# PWM_sheild_d1_mini_v1.net
KiCad netlist of a schematic drawn in EAGLE
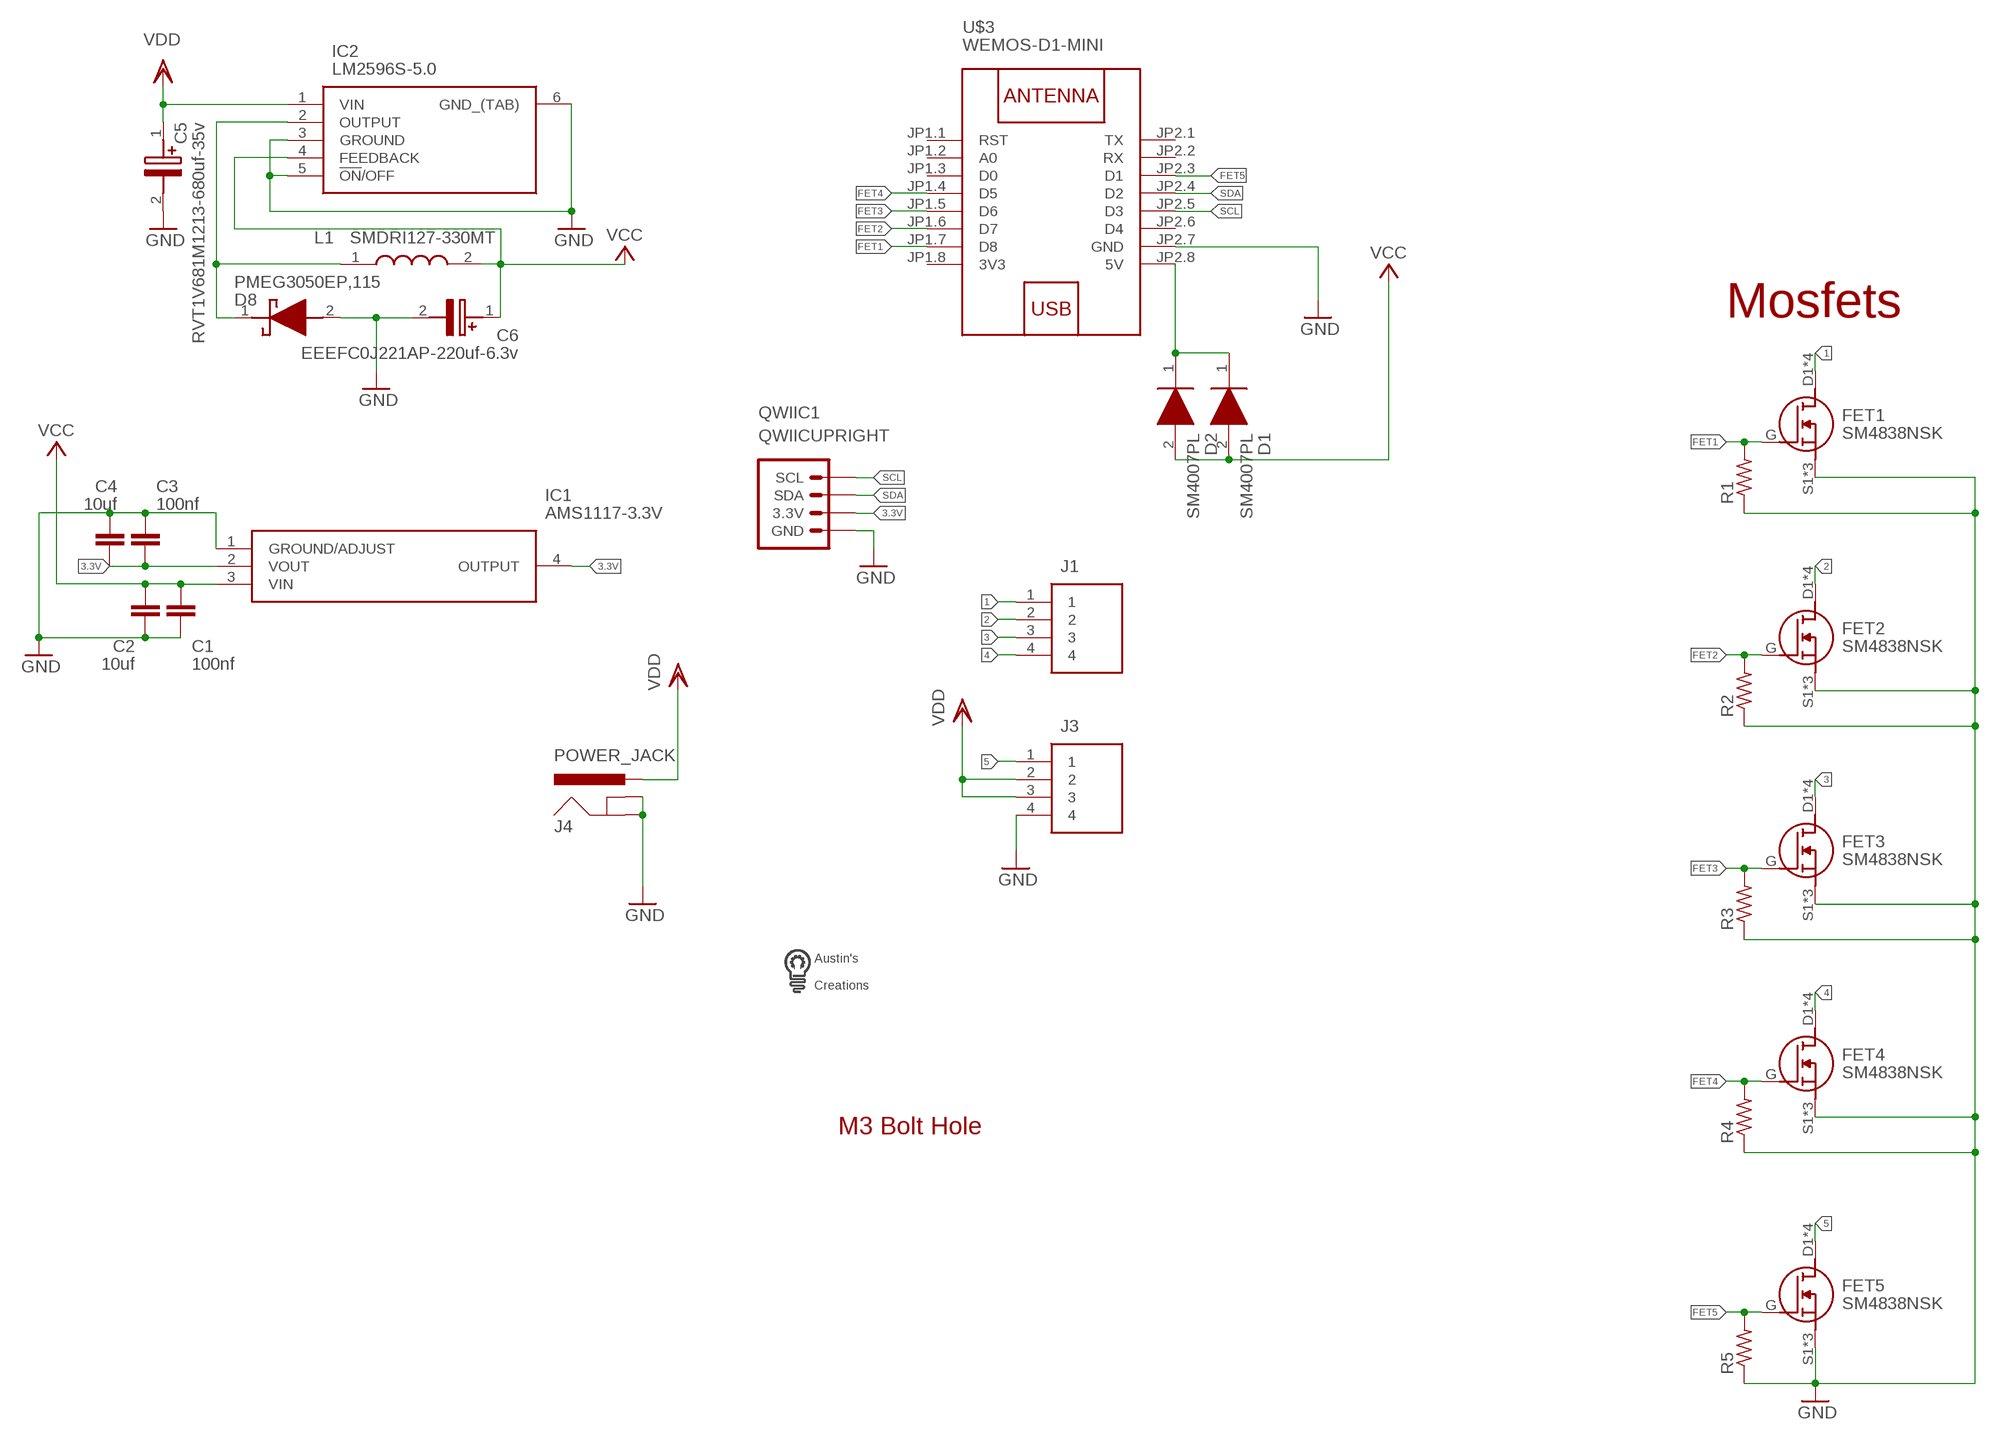
[diagram p0: schematic, sheet 1]

(export (version "E")
  (design (tool "Eeschema 10.0.6"))
  (components
    (comp (ref "C1")
      (value "100nf")
      (footprint "eagle-import:C0603")
      (libsource (lib "eagle-import") (part "C-EUC0603"))
    )
    (comp (ref "C2")
      (value "10uf")
      (footprint "eagle-import:C0603")
      (libsource (lib "eagle-import") (part "C-EUC0603"))
    )
    (comp (ref "C3")
      (value "100nf")
      (footprint "eagle-import:C0603")
      (libsource (lib "eagle-import") (part "C-EUC0603"))
    )
    (comp (ref "C4")
      (value "10uf")
      (footprint "eagle-import:C0603")
      (libsource (lib "eagle-import") (part "C-EUC0603"))
    )
    (comp (ref "C5")
      (value "RVT1V681M1213-680uf-35v")
      (footprint "eagle-import:CAPAE1350X1400N")
      (fields
        (field (name "MANUFACTURER_PART_NUMBER") "EEE-HD1V681AQ")
        (field (name "MOUSER_PART_NUMBER") "667-EEE-HD1V681AQ")
      )
      (libsource (lib "eagle-import") (part "EEE-HD1V681AQ"))
    )
    (comp (ref "C6")
      (value "EEEFC0J221AP-220uf-6.3v")
      (footprint "eagle-import:CAPAE830X650N")
      (fields (field (name "MANUFACTURER_PART_NUMBER") "EEEFC0J221AP"))
      (libsource (lib "eagle-import") (part "EEEFC0J221AP"))
    )
    (comp (ref "D1")
      (value "SM4007PL")
      (footprint "eagle-import:SODFL3718X125N")
      (libsource (lib "eagle-import") (part "SM4007PL"))
    )
    (comp (ref "D2")
      (value "SM4007PL")
      (footprint "eagle-import:SODFL3718X125N")
      (libsource (lib "eagle-import") (part "SM4007PL"))
    )
    (comp (ref "D8")
      (value "PMEG3050EP,115")
      (footprint "eagle-import:PMEG3050EP115")
      (fields (field (name "MOUSER_PART_NUMBER") "771-PMEG3050EP115"))
      (libsource (lib "eagle-import") (part "PMEG3050EP,115"))
    )
    (comp (ref "FET1")
      (value "SM4838NSK")
      (footprint "eagle-import:SM4838NSK")
      (libsource (lib "eagle-import") (part "SM4838NSK"))
    )
    (comp (ref "FET2")
      (value "SM4838NSK")
      (footprint "eagle-import:SM4838NSK")
      (libsource (lib "eagle-import") (part "SM4838NSK"))
    )
    (comp (ref "FET3")
      (value "SM4838NSK")
      (footprint "eagle-import:SM4838NSK")
      (libsource (lib "eagle-import") (part "SM4838NSK"))
    )
    (comp (ref "FET4")
      (value "SM4838NSK")
      (footprint "eagle-import:SM4838NSK")
      (libsource (lib "eagle-import") (part "SM4838NSK"))
    )
    (comp (ref "FET5")
      (value "SM4838NSK")
      (footprint "eagle-import:SM4838NSK")
      (libsource (lib "eagle-import") (part "SM4838NSK"))
    )
    (comp (ref "IC1")
      (value "AMS1117-3.3V")
      (footprint "eagle-import:SOT229P700X180-4N")
      (fields (field (name "MANUFACTURER_PART_NUMBER") "ams1117-3.3v"))
      (libsource (lib "eagle-import") (part "AMS1117-3.3V"))
    )
    (comp (ref "IC2")
      (value "LM2596S-5.0")
      (footprint "eagle-import:TO170P1435X465-6N")
      (fields
        (field (name "MANUFACTURER_PART_NUMBER") "LM2596S-3.3/NOPB")
        (field (name "MOUSER_PART_NUMBER") "926-LM2596S-3.3/NOPB")
      )
      (libsource (lib "eagle-import") (part "LM2596S-3.3_NOPB"))
    )
    (comp (ref "J1")
      (value "SCREWTERMINAL-4P-5MM")
      (footprint "eagle-import:SCREWTERMINAL-4P-5MM")
      (fields
        (field (name "MANUFACTURER_PART_NUMBER") "TB001-500-04BE")
        (field (name "MOUSER_PART_NUMBER") "490-TB001-500-04BE")
      )
      (libsource (lib "eagle-import") (part "SCREWTERMINAL-4P-5MM"))
    )
    (comp (ref "J3")
      (value "SCREWTERMINAL-4P-5MM")
      (footprint "eagle-import:SCREWTERMINAL-4P-5MM")
      (fields
        (field (name "MANUFACTURER_PART_NUMBER") "TB001-500-04BE")
        (field (name "MOUSER_PART_NUMBER") "490-TB001-500-04BE")
      )
      (libsource (lib "eagle-import") (part "SCREWTERMINAL-4P-5MM"))
    )
    (comp (ref "J4")
      (value "POWER_JACK")
      (footprint "eagle-import:POWER_JACK_PTH")
      (libsource (lib "eagle-import") (part "POWER_JACK"))
    )
    (comp (ref "L1")
      (value "SMDRI127-330MT")
      (footprint "eagle-import:INDPM120120X800N")
      (fields
        (field (name "MANUFACTURER_PART_NUMBER") "CDRH127/LDNP-330MC")
        (field (name "MOUSER_PART_NUMBER") "851-CDRH127LDNP330MC")
      )
      (libsource (lib "eagle-import") (part "CDRH127_LDNP-330MC"))
    )
    (comp (ref "QWIIC1")
      (value "QWIICUPRIGHT")
      (footprint "eagle-import:BM04B-SRSS-TB")
      (libsource (lib "eagle-import") (part "QWIICUPRIGHT"))
    )
    (comp (ref "R1")
      (value "R-US_R0603")
      (footprint "eagle-import:R0603")
      (libsource (lib "eagle-import") (part "R-US_R0603"))
    )
    (comp (ref "R2")
      (value "R-US_R0603")
      (footprint "eagle-import:R0603")
      (libsource (lib "eagle-import") (part "R-US_R0603"))
    )
    (comp (ref "R3")
      (value "R-US_R0603")
      (footprint "eagle-import:R0603")
      (libsource (lib "eagle-import") (part "R-US_R0603"))
    )
    (comp (ref "R4")
      (value "R-US_R0603")
      (footprint "eagle-import:R0603")
      (libsource (lib "eagle-import") (part "R-US_R0603"))
    )
    (comp (ref "R5")
      (value "R-US_R0603")
      (footprint "eagle-import:R0603")
      (libsource (lib "eagle-import") (part "R-US_R0603"))
    )
    (comp (ref "U$1")
      (value "M3BOLTHOLE")
      (footprint "eagle-import:M3BOLTHOLE")
      (libsource (lib "eagle-import") (part "M3BOLTHOLE"))
    )
    (comp (ref "U$3")
      (value "WEMOS-D1-MINI")
      (footprint "eagle-import:WEMOS-D1-MINI")
      (libsource (lib "eagle-import") (part "WEMOS-D1-MINI"))
    )
    (comp (ref "U$4")
      (value "LOGOMED")
      (footprint "eagle-import:LOGOMED")
      (libsource (lib "eagle-import") (part "LOGOMED"))
    )
  )
  (nets
    (net (code "1") (name "/3V3") (class "Default")
      (node (ref "U$3") (pin "JP1.8") (pinfunction "3V3_JP1.8") (pintype "power_in"))
    )
    (net (code "2") (name "1") (class "Default")
      (node (ref "FET1") (pin "D1") (pinfunction "D_D1") (pintype "bidirectional"))
      (node (ref "FET1") (pin "D2") (pinfunction "D_D2") (pintype "bidirectional"))
      (node (ref "FET1") (pin "D3") (pinfunction "D_D3") (pintype "bidirectional"))
      (node (ref "FET1") (pin "D4") (pinfunction "D_D4") (pintype "bidirectional"))
      (node (ref "J1") (pin "1") (pinfunction "1_1") (pintype "bidirectional"))
    )
    (net (code "3") (name "2") (class "Default")
      (node (ref "FET2") (pin "D1") (pinfunction "D_D1") (pintype "bidirectional"))
      (node (ref "FET2") (pin "D2") (pinfunction "D_D2") (pintype "bidirectional"))
      (node (ref "FET2") (pin "D3") (pinfunction "D_D3") (pintype "bidirectional"))
      (node (ref "FET2") (pin "D4") (pinfunction "D_D4") (pintype "bidirectional"))
      (node (ref "J1") (pin "2") (pinfunction "2_2") (pintype "bidirectional"))
    )
    (net (code "4") (name "3") (class "Default")
      (node (ref "FET3") (pin "D1") (pinfunction "D_D1") (pintype "bidirectional"))
      (node (ref "FET3") (pin "D2") (pinfunction "D_D2") (pintype "bidirectional"))
      (node (ref "FET3") (pin "D3") (pinfunction "D_D3") (pintype "bidirectional"))
      (node (ref "FET3") (pin "D4") (pinfunction "D_D4") (pintype "bidirectional"))
      (node (ref "J1") (pin "3") (pinfunction "3_3") (pintype "bidirectional"))
    )
    (net (code "5") (name "3.3V") (class "Default")
      (node (ref "C3") (pin "2") (pinfunction "2_2") (pintype "passive"))
      (node (ref "C4") (pin "2") (pinfunction "2_2") (pintype "passive"))
      (node (ref "IC1") (pin "2") (pinfunction "VOUT_2") (pintype "bidirectional"))
      (node (ref "IC1") (pin "4") (pinfunction "OUTPUT_4") (pintype "bidirectional"))
      (node (ref "QWIIC1") (pin "2") (pinfunction "3.3V_2") (pintype "passive"))
    )
    (net (code "6") (name "4") (class "Default")
      (node (ref "FET4") (pin "D1") (pinfunction "D_D1") (pintype "bidirectional"))
      (node (ref "FET4") (pin "D2") (pinfunction "D_D2") (pintype "bidirectional"))
      (node (ref "FET4") (pin "D3") (pinfunction "D_D3") (pintype "bidirectional"))
      (node (ref "FET4") (pin "D4") (pinfunction "D_D4") (pintype "bidirectional"))
      (node (ref "J1") (pin "4") (pinfunction "4_4") (pintype "bidirectional"))
    )
    (net (code "7") (name "5") (class "Default")
      (node (ref "FET5") (pin "D1") (pinfunction "D_D1") (pintype "bidirectional"))
      (node (ref "FET5") (pin "D2") (pinfunction "D_D2") (pintype "bidirectional"))
      (node (ref "FET5") (pin "D3") (pinfunction "D_D3") (pintype "bidirectional"))
      (node (ref "FET5") (pin "D4") (pinfunction "D_D4") (pintype "bidirectional"))
      (node (ref "J3") (pin "1") (pinfunction "1_1") (pintype "bidirectional"))
    )
    (net (code "8") (name "FET1") (class "Default")
      (node (ref "FET1") (pin "G") (pinfunction "G_G") (pintype "bidirectional"))
      (node (ref "R1") (pin "2") (pinfunction "2_2") (pintype "passive"))
      (node (ref "U$3") (pin "JP1.7") (pinfunction "D8_JP1.7") (pintype "bidirectional"))
    )
    (net (code "9") (name "FET2") (class "Default")
      (node (ref "FET2") (pin "G") (pinfunction "G_G") (pintype "bidirectional"))
      (node (ref "R2") (pin "2") (pinfunction "2_2") (pintype "passive"))
      (node (ref "U$3") (pin "JP1.6") (pinfunction "D7_JP1.6") (pintype "bidirectional"))
    )
    (net (code "10") (name "FET3") (class "Default")
      (node (ref "FET3") (pin "G") (pinfunction "G_G") (pintype "bidirectional"))
      (node (ref "R3") (pin "2") (pinfunction "2_2") (pintype "passive"))
      (node (ref "U$3") (pin "JP1.5") (pinfunction "D6_JP1.5") (pintype "bidirectional"))
    )
    (net (code "11") (name "FET4") (class "Default")
      (node (ref "FET4") (pin "G") (pinfunction "G_G") (pintype "bidirectional"))
      (node (ref "R4") (pin "2") (pinfunction "2_2") (pintype "passive"))
      (node (ref "U$3") (pin "JP1.4") (pinfunction "D5_JP1.4") (pintype "bidirectional"))
    )
    (net (code "12") (name "FET5") (class "Default")
      (node (ref "FET5") (pin "G") (pinfunction "G_G") (pintype "bidirectional"))
      (node (ref "R5") (pin "2") (pinfunction "2_2") (pintype "passive"))
      (node (ref "U$3") (pin "JP2.3") (pinfunction "D1_JP2.3") (pintype "bidirectional"))
    )
    (net (code "13") (name "GND") (class "Default")
      (node (ref "C1") (pin "2") (pinfunction "2_2") (pintype "passive"))
      (node (ref "C2") (pin "2") (pinfunction "2_2") (pintype "passive"))
      (node (ref "C3") (pin "1") (pinfunction "1_1") (pintype "passive"))
      (node (ref "C4") (pin "1") (pinfunction "1_1") (pintype "passive"))
      (node (ref "C5") (pin "2") (pinfunction "-_2") (pintype "bidirectional"))
      (node (ref "C6") (pin "2") (pinfunction "-_2") (pintype "bidirectional"))
      (node (ref "D8") (pin "2") (pinfunction "A_2") (pintype "bidirectional"))
      (node (ref "FET1") (pin "S1") (pinfunction "S_S1") (pintype "bidirectional"))
      (node (ref "FET1") (pin "S2") (pinfunction "S_S2") (pintype "bidirectional"))
      (node (ref "FET1") (pin "S3") (pinfunction "S_S3") (pintype "bidirectional"))
      (node (ref "FET2") (pin "S1") (pinfunction "S_S1") (pintype "bidirectional"))
      (node (ref "FET2") (pin "S2") (pinfunction "S_S2") (pintype "bidirectional"))
      (node (ref "FET2") (pin "S3") (pinfunction "S_S3") (pintype "bidirectional"))
      (node (ref "FET3") (pin "S1") (pinfunction "S_S1") (pintype "bidirectional"))
      (node (ref "FET3") (pin "S2") (pinfunction "S_S2") (pintype "bidirectional"))
      (node (ref "FET3") (pin "S3") (pinfunction "S_S3") (pintype "bidirectional"))
      (node (ref "FET4") (pin "S1") (pinfunction "S_S1") (pintype "bidirectional"))
      (node (ref "FET4") (pin "S2") (pinfunction "S_S2") (pintype "bidirectional"))
      (node (ref "FET4") (pin "S3") (pinfunction "S_S3") (pintype "bidirectional"))
      (node (ref "FET5") (pin "S1") (pinfunction "S_S1") (pintype "bidirectional"))
      (node (ref "FET5") (pin "S2") (pinfunction "S_S2") (pintype "bidirectional"))
      (node (ref "FET5") (pin "S3") (pinfunction "S_S3") (pintype "bidirectional"))
      (node (ref "IC1") (pin "1") (pinfunction "GROUND/ADJUST_1") (pintype "bidirectional"))
      (node (ref "IC2") (pin "3") (pinfunction "GROUND_3") (pintype "bidirectional"))
      (node (ref "IC2") (pin "5") (pinfunction "~{ON}/OFF_5") (pintype "bidirectional"))
      (node (ref "IC2") (pin "6") (pinfunction "GND_(TAB)_6") (pintype "power_in"))
      (node (ref "J3") (pin "4") (pinfunction "4_4") (pintype "bidirectional"))
      (node (ref "J4") (pin "GND") (pinfunction "GND_GND") (pintype "bidirectional"))
      (node (ref "J4") (pin "GNDBREAK") (pinfunction "GNDBREAK_GNDBREAK") (pintype "bidirectional"))
      (node (ref "QWIIC1") (pin "1") (pinfunction "GND_1") (pintype "passive"))
      (node (ref "R1") (pin "1") (pinfunction "1_1") (pintype "passive"))
      (node (ref "R2") (pin "1") (pinfunction "1_1") (pintype "passive"))
      (node (ref "R3") (pin "1") (pinfunction "1_1") (pintype "passive"))
      (node (ref "R4") (pin "1") (pinfunction "1_1") (pintype "passive"))
      (node (ref "R5") (pin "1") (pinfunction "1_1") (pintype "passive"))
      (node (ref "U$3") (pin "JP2.7") (pinfunction "GND_JP2.7") (pintype "power_in"))
    )
    (net (code "14") (name "Net-(D1-K)") (class "Default")
      (node (ref "D1") (pin "1") (pinfunction "K_1") (pintype "bidirectional"))
      (node (ref "D2") (pin "1") (pinfunction "K_1") (pintype "bidirectional"))
      (node (ref "U$3") (pin "JP2.8") (pinfunction "5V_JP2.8") (pintype "power_in"))
    )
    (net (code "15") (name "Net-(D8-K)") (class "Default")
      (node (ref "D8") (pin "1") (pinfunction "K_1") (pintype "bidirectional"))
      (node (ref "IC2") (pin "2") (pinfunction "OUTPUT_2") (pintype "output"))
      (node (ref "L1") (pin "1") (pinfunction "1_1") (pintype "bidirectional"))
    )
    (net (code "16") (name "SCL") (class "Default")
      (node (ref "QWIIC1") (pin "4") (pinfunction "SCL_4") (pintype "passive"))
      (node (ref "U$3") (pin "JP2.5") (pinfunction "D3_JP2.5") (pintype "bidirectional"))
    )
    (net (code "17") (name "SDA") (class "Default")
      (node (ref "QWIIC1") (pin "3") (pinfunction "SDA_3") (pintype "passive"))
      (node (ref "U$3") (pin "JP2.4") (pinfunction "D2_JP2.4") (pintype "bidirectional"))
    )
    (net (code "18") (name "VCC") (class "Default")
      (node (ref "C1") (pin "1") (pinfunction "1_1") (pintype "passive"))
      (node (ref "C2") (pin "1") (pinfunction "1_1") (pintype "passive"))
      (node (ref "C6") (pin "1") (pinfunction "+_1") (pintype "bidirectional"))
      (node (ref "D1") (pin "2") (pinfunction "A_2") (pintype "bidirectional"))
      (node (ref "D2") (pin "2") (pinfunction "A_2") (pintype "bidirectional"))
      (node (ref "IC1") (pin "3") (pinfunction "VIN_3") (pintype "bidirectional"))
      (node (ref "IC2") (pin "4") (pinfunction "FEEDBACK_4") (pintype "bidirectional"))
      (node (ref "L1") (pin "2") (pinfunction "2_2") (pintype "bidirectional"))
    )
    (net (code "19") (name "VDD") (class "Default")
      (node (ref "C5") (pin "1") (pinfunction "+_1") (pintype "bidirectional"))
      (node (ref "IC2") (pin "1") (pinfunction "VIN_1") (pintype "input"))
      (node (ref "J3") (pin "2") (pinfunction "2_2") (pintype "bidirectional"))
      (node (ref "J3") (pin "3") (pinfunction "3_3") (pintype "bidirectional"))
      (node (ref "J4") (pin "PWR") (pinfunction "PWR_PWR") (pintype "bidirectional"))
    )
    (net (code "20") (name "unconnected-(U$3-A0-PadJP1.2)") (class "Default")
      (node (ref "U$3") (pin "JP1.2") (pinfunction "A0_JP1.2") (pintype "bidirectional"))
    )
    (net (code "21") (name "unconnected-(U$3-D0-PadJP1.3)") (class "Default")
      (node (ref "U$3") (pin "JP1.3") (pinfunction "D0_JP1.3") (pintype "bidirectional"))
    )
    (net (code "22") (name "unconnected-(U$3-D4-PadJP2.6)") (class "Default")
      (node (ref "U$3") (pin "JP2.6") (pinfunction "D4_JP2.6") (pintype "bidirectional"))
    )
    (net (code "23") (name "unconnected-(U$3-RST-PadJP1.1)") (class "Default")
      (node (ref "U$3") (pin "JP1.1") (pinfunction "RST_JP1.1") (pintype "bidirectional"))
    )
    (net (code "24") (name "unconnected-(U$3-RX-PadJP2.2)") (class "Default")
      (node (ref "U$3") (pin "JP2.2") (pinfunction "RX_JP2.2") (pintype "bidirectional"))
    )
    (net (code "25") (name "unconnected-(U$3-TX-PadJP2.1)") (class "Default")
      (node (ref "U$3") (pin "JP2.1") (pinfunction "TX_JP2.1") (pintype "bidirectional"))
    )
  )
)
